# ProPrj_hackercard_2025-04-09.net
KiCad netlist of a schematic drawn in EasyEDA Pro
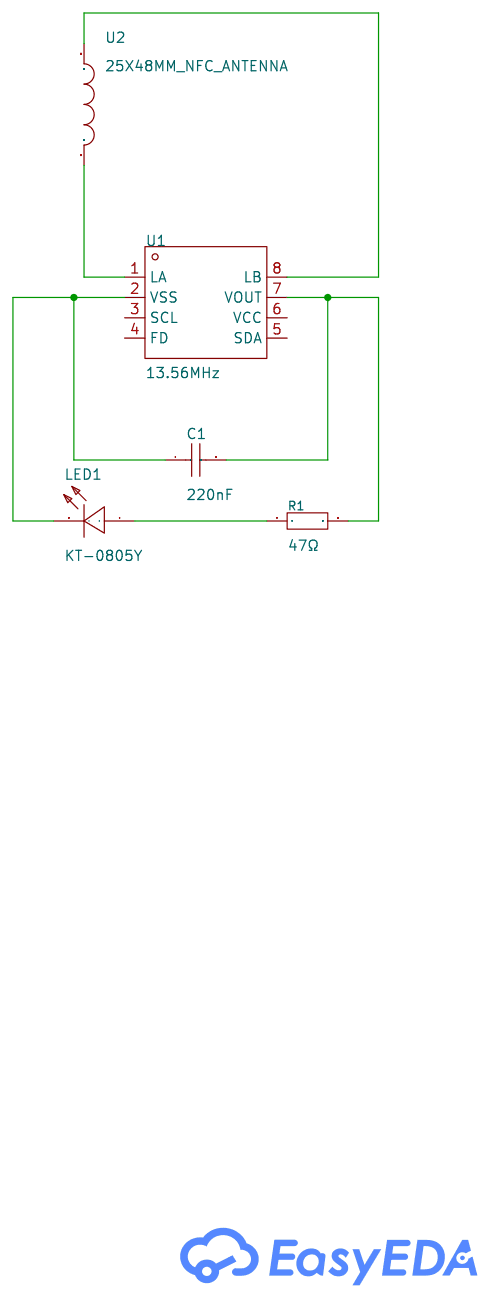
[diagram p0: schematic sheet]

(export (version "E")
  (design (tool "Eeschema 10.0.6"))
  (components
    (comp (ref "C1")
      (value "220nF")
      (footprint "easyedapro:C0603")
      (fields
        (field (name "Manufacturer Part") "CL10B224KA8NNNC")
        (field (name "Manufacturer") "SAMSUNG(三星)")
      )
      (libsource (lib "easyedapro") (part "CL10B224KA8NNNC"))
    )
    (comp (ref "LED1")
      (value "KT-0805Y")
      (footprint "easyedapro:LED0805-R-RD")
      (fields (field (name "Manufacturer") "KENTO"))
      (libsource (lib "easyedapro") (part "17-21SUYC/TR8"))
    )
    (comp (ref "R1")
      (value "47Ω")
      (footprint "easyedapro:R0603")
      (fields
        (field (name "Manufacturer Part") "0603WAF470JT5E")
        (field (name "Manufacturer") "UNI-ROYAL(厚声)")
      )
      (libsource (lib "easyedapro") (part "0603WAF470JT5E"))
    )
    (comp (ref "U1")
      (value "13.56MHz")
      (footprint "easyedapro:XQFN-8_L1.6-W1.6-P0.50-BL_NT3H2111W0FHKH")
      (fields (field (name "Manufacturer Part") "NT3H2111W0FHKH") (field (name "Manufacturer") "NXP(恩智浦)"))
      (libsource (lib "easyedapro") (part "NT3H2111W0FHKH"))
    )
    (comp (ref "U2")
      (value "25X48MM_NFC_ANTENNA")
      (footprint "easyedapro:25X48MM_NFC_ANTENNA")
      (libsource (lib "easyedapro") (part "25X48MM_NFC_ANTENNA"))
    )
  )
  (nets
    (net (code "1") (name "Net-(LED1-+)") (class "Default")
      (node (ref "LED1") (pin "1") (pinfunction "+_1") (pintype "unspecified"))
      (node (ref "R1") (pin "1") (pinfunction "1_1") (pintype "input"))
    )
    (net (code "2") (name "Net-(LED1--)") (class "Default")
      (node (ref "C1") (pin "1") (pinfunction "1_1") (pintype "input"))
      (node (ref "LED1") (pin "2") (pinfunction "-_2") (pintype "unspecified"))
      (node (ref "U1") (pin "2") (pinfunction "VSS_2") (pintype "unspecified"))
    )
    (net (code "3") (name "Net-(U1-LA)") (class "Default")
      (node (ref "U1") (pin "1") (pinfunction "LA_1") (pintype "unspecified"))
      (node (ref "U2") (pin "P$2") (pinfunction "P$2_P$2") (pintype "bidirectional"))
    )
    (net (code "4") (name "Net-(U1-LB)") (class "Default")
      (node (ref "U1") (pin "8") (pinfunction "LB_8") (pintype "unspecified"))
      (node (ref "U2") (pin "P$1") (pinfunction "P$1_P$1") (pintype "bidirectional"))
    )
    (net (code "5") (name "Net-(U1-VOUT)") (class "Default")
      (node (ref "C1") (pin "2") (pinfunction "2_2") (pintype "input"))
      (node (ref "R1") (pin "2") (pinfunction "2_2") (pintype "input"))
      (node (ref "U1") (pin "7") (pinfunction "VOUT_7") (pintype "unspecified"))
    )
    (net (code "6") (name "unconnected-(U1-FD-Pad4)") (class "Default")
      (node (ref "U1") (pin "4") (pinfunction "FD_4") (pintype "unspecified"))
    )
    (net (code "7") (name "unconnected-(U1-SCL-Pad3)") (class "Default")
      (node (ref "U1") (pin "3") (pinfunction "SCL_3") (pintype "unspecified"))
    )
    (net (code "8") (name "unconnected-(U1-SDA-Pad5)") (class "Default")
      (node (ref "U1") (pin "5") (pinfunction "SDA_5") (pintype "unspecified"))
    )
    (net (code "9") (name "unconnected-(U1-VCC-Pad6)") (class "Default")
      (node (ref "U1") (pin "6") (pinfunction "VCC_6") (pintype "unspecified"))
    )
  )
)
